# Power_Buggy_EFI_V3_1.net
KiCad netlist of a schematic drawn in EAGLE
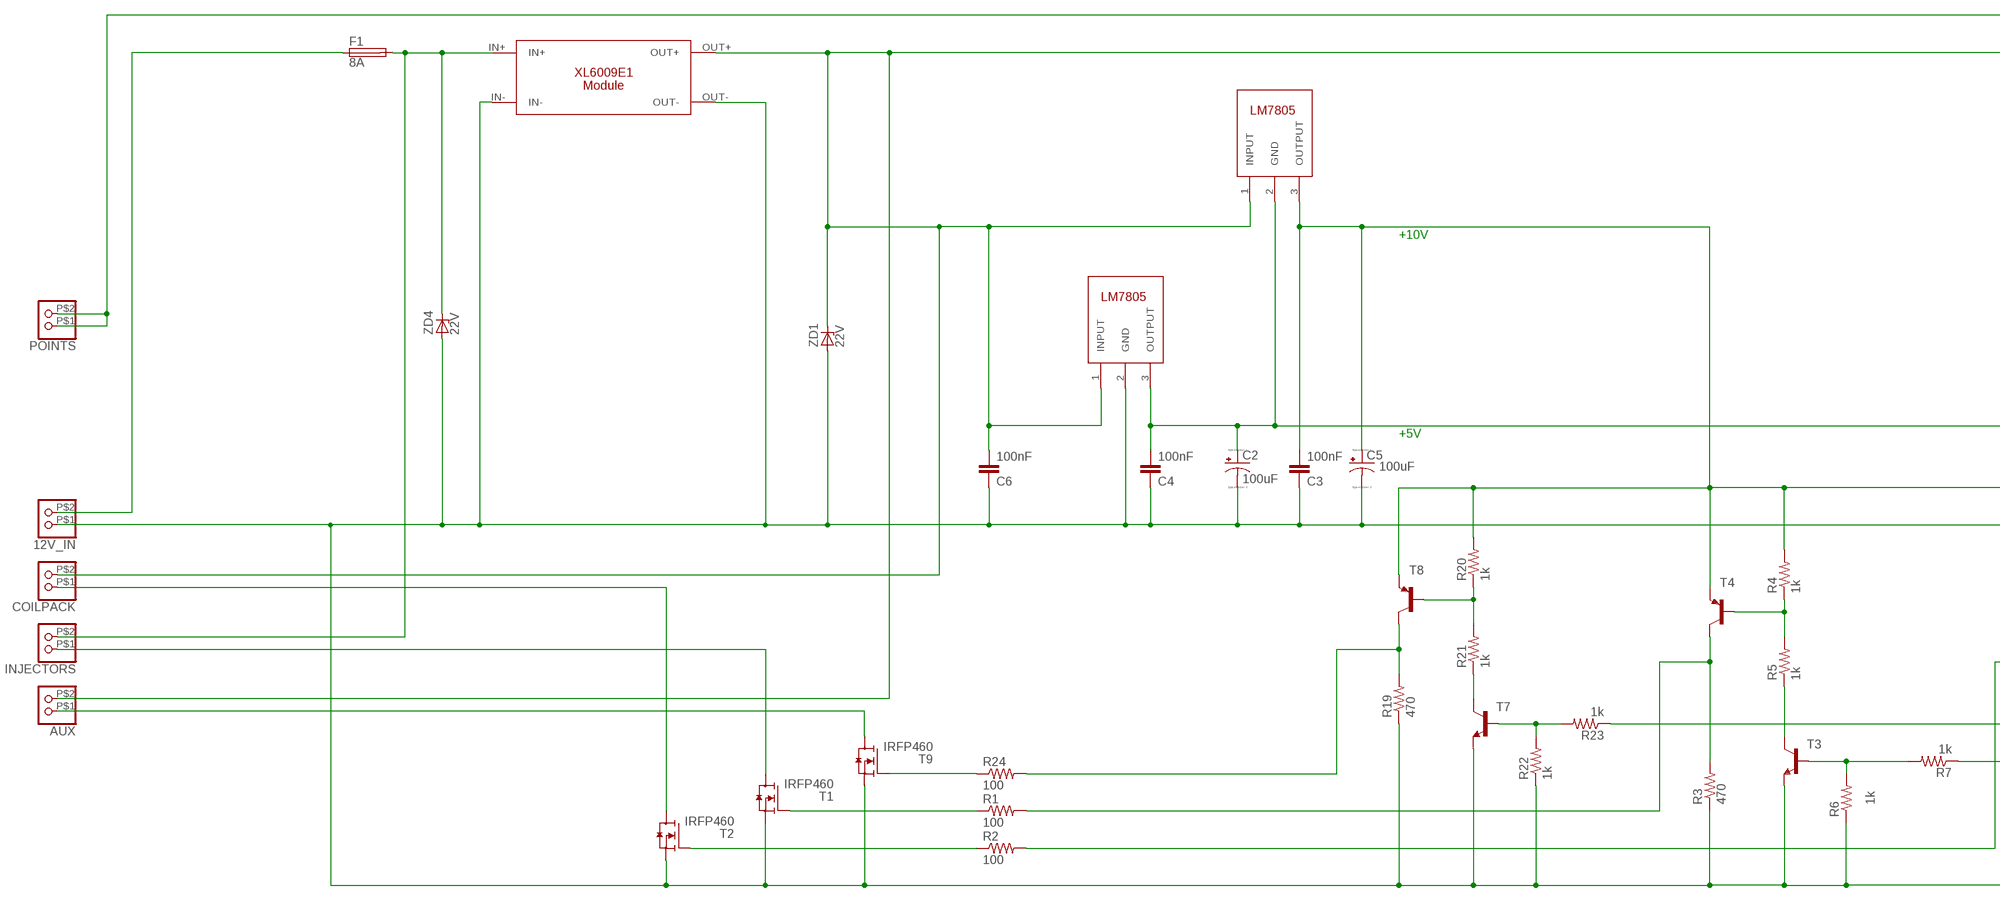
[diagram p0: schematic, sheet 1, part 1 of 2]
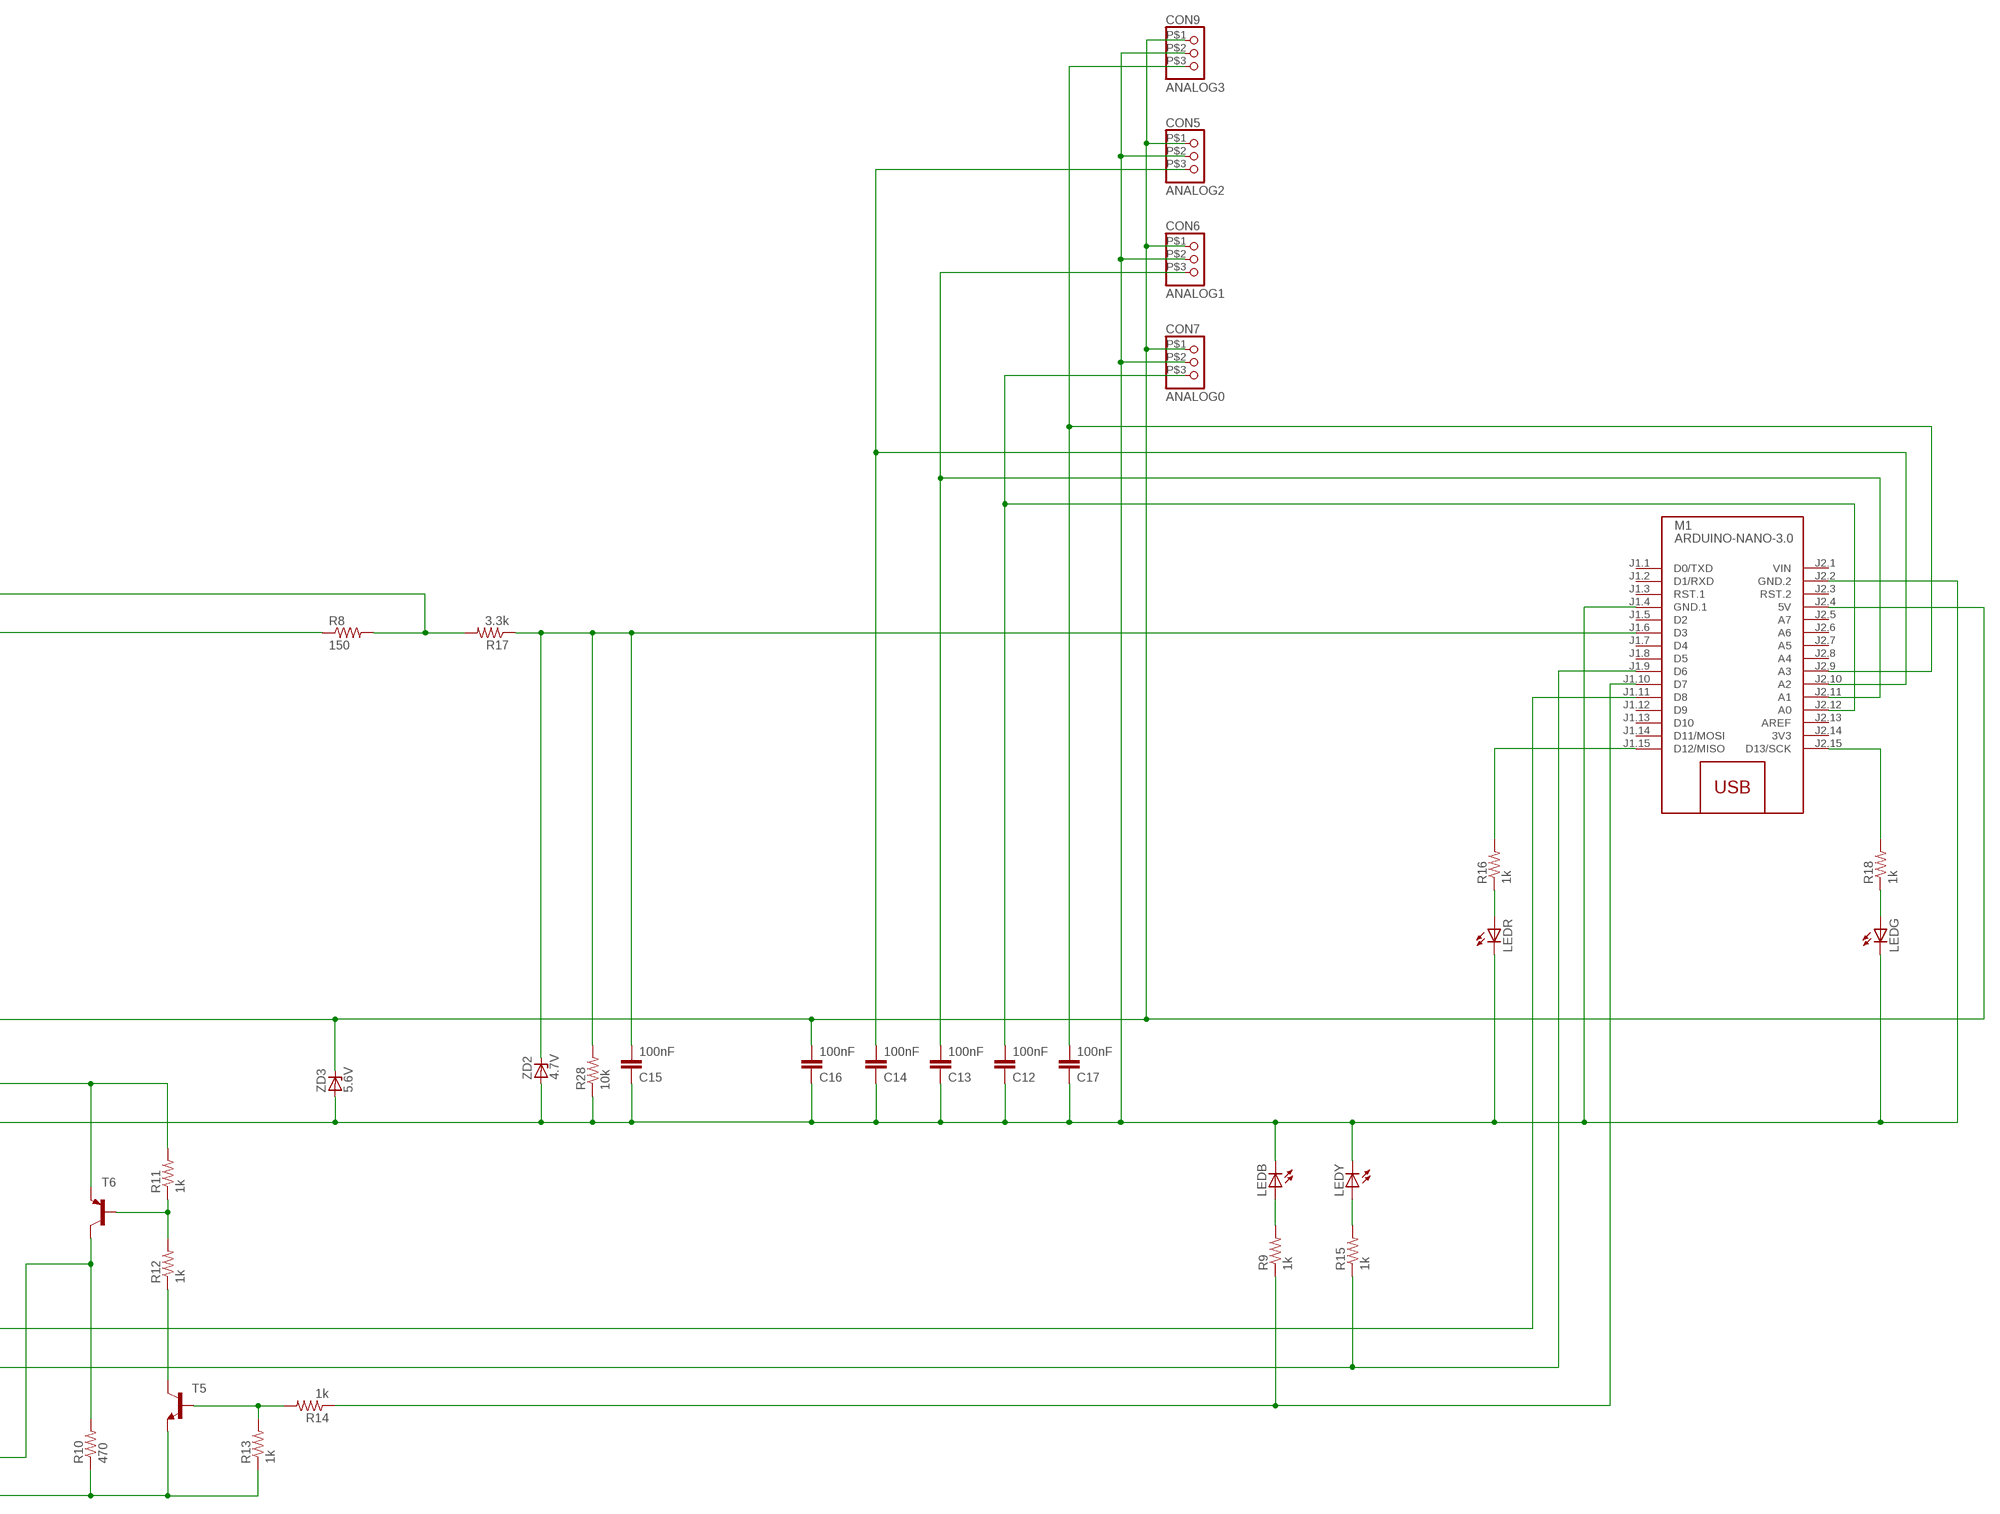
[diagram p1: schematic, sheet 1, part 2 of 2]

(export (version "E")
  (design (tool "Eeschema 10.0.6"))
  (components
    (comp (ref "12V_IN")
      (value "EBBA-02-C-SS-BU")
      (footprint "eagle-import:EBBA-02-C-SS-BU")
      (libsource (lib "eagle-import") (part "EBBA-02-C-SS-BU"))
    )
    (comp (ref "AUX")
      (value "EBBA-02-C-SS-BU")
      (footprint "eagle-import:EBBA-02-C-SS-BU")
      (libsource (lib "eagle-import") (part "EBBA-02-C-SS-BU"))
    )
    (comp (ref "C2")
      (value "100uF")
      (footprint "eagle-import:E2-5")
      (libsource (lib "eagle-import") (part "CPOL-USE2-5"))
    )
    (comp (ref "C3")
      (value "100nF")
      (footprint "eagle-import:C050-025X075")
      (libsource (lib "eagle-import") (part "C-EU050-025X075"))
    )
    (comp (ref "C4")
      (value "100nF")
      (footprint "eagle-import:C050-025X075")
      (libsource (lib "eagle-import") (part "C-EU050-025X075"))
    )
    (comp (ref "C5")
      (value "100uF")
      (footprint "eagle-import:E2-5")
      (libsource (lib "eagle-import") (part "CPOL-USE2-5"))
    )
    (comp (ref "C6")
      (value "100nF")
      (footprint "eagle-import:C050-025X075")
      (libsource (lib "eagle-import") (part "C-EU050-025X075"))
    )
    (comp (ref "C12")
      (value "100nF")
      (footprint "eagle-import:C050-025X075")
      (libsource (lib "eagle-import") (part "C-EU050-025X075"))
    )
    (comp (ref "C13")
      (value "100nF")
      (footprint "eagle-import:C050-025X075")
      (libsource (lib "eagle-import") (part "C-EU050-025X075"))
    )
    (comp (ref "C14")
      (value "100nF")
      (footprint "eagle-import:C050-025X075")
      (libsource (lib "eagle-import") (part "C-EU050-025X075"))
    )
    (comp (ref "C15")
      (value "100nF")
      (footprint "eagle-import:C050-025X075")
      (libsource (lib "eagle-import") (part "C-EU050-025X075"))
    )
    (comp (ref "C16")
      (value "100nF")
      (footprint "eagle-import:C050-025X075")
      (libsource (lib "eagle-import") (part "C-EU050-025X075"))
    )
    (comp (ref "C17")
      (value "100nF")
      (footprint "eagle-import:C050-025X075")
      (libsource (lib "eagle-import") (part "C-EU050-025X075"))
    )
    (comp (ref "COILPACK")
      (value "EBBA-02-C-SS-BU")
      (footprint "eagle-import:EBBA-02-C-SS-BU")
      (libsource (lib "eagle-import") (part "EBBA-02-C-SS-BU"))
    )
    (comp (ref "CON5")
      (value "ANALOG2")
      (footprint "eagle-import:2.0MM_X3")
      (libsource (lib "eagle-import") (part "2.0MM_X3"))
    )
    (comp (ref "CON6")
      (value "ANALOG1")
      (footprint "eagle-import:2.0MM_X3")
      (libsource (lib "eagle-import") (part "2.0MM_X3"))
    )
    (comp (ref "CON7")
      (value "ANALOG0")
      (footprint "eagle-import:2.0MM_X3")
      (libsource (lib "eagle-import") (part "2.0MM_X3"))
    )
    (comp (ref "CON9")
      (value "ANALOG3")
      (footprint "eagle-import:2.0MM_X3")
      (libsource (lib "eagle-import") (part "2.0MM_X3"))
    )
    (comp (ref "F1")
      (value "8A")
      (footprint "eagle-import:GSH15")
      (fields (field (name "MPN") "64900001039"))
      (libsource (lib "eagle-import") (part "GSH15"))
    )
    (comp (ref "INJECTORS")
      (value "EBBA-02-C-SS-BU")
      (footprint "eagle-import:EBBA-02-C-SS-BU")
      (libsource (lib "eagle-import") (part "EBBA-02-C-SS-BU"))
    )
    (comp (ref "LEDB")
      (value "LED3MM")
      (footprint "eagle-import:LED3MM")
      (libsource (lib "eagle-import") (part "LED3MM"))
    )
    (comp (ref "LEDG")
      (value "LED3MM")
      (footprint "eagle-import:LED3MM")
      (libsource (lib "eagle-import") (part "LED3MM"))
    )
    (comp (ref "LEDR")
      (value "LED3MM")
      (footprint "eagle-import:LED3MM")
      (libsource (lib "eagle-import") (part "LED3MM"))
    )
    (comp (ref "LEDY")
      (value "LED3MM")
      (footprint "eagle-import:LED3MM")
      (libsource (lib "eagle-import") (part "LED3MM"))
    )
    (comp (ref "M1")
      (value "ARDUINO-NANO-3.0")
      (footprint "eagle-import:ARDUINO-NANO-3.0")
      (libsource (lib "eagle-import") (part "ARDUINO-NANO-3.0"))
    )
    (comp (ref "POINTS")
      (value "EBBA-02-C-SS-BU")
      (footprint "eagle-import:EBBA-02-C-SS-BU")
      (libsource (lib "eagle-import") (part "EBBA-02-C-SS-BU"))
    )
    (comp (ref "R1")
      (value "100")
      (footprint "eagle-import:0207_10")
      (libsource (lib "eagle-import") (part "R-US_0207/10"))
    )
    (comp (ref "R2")
      (value "100")
      (footprint "eagle-import:0207_10")
      (libsource (lib "eagle-import") (part "R-US_0207/10"))
    )
    (comp (ref "R3")
      (value "470")
      (footprint "eagle-import:0207_10")
      (libsource (lib "eagle-import") (part "R-US_0207/10"))
    )
    (comp (ref "R4")
      (value "1k")
      (footprint "eagle-import:0207_10")
      (libsource (lib "eagle-import") (part "R-US_0207/10"))
    )
    (comp (ref "R5")
      (value "1k")
      (footprint "eagle-import:0207_10")
      (libsource (lib "eagle-import") (part "R-US_0207/10"))
    )
    (comp (ref "R6")
      (value "1k")
      (footprint "eagle-import:0207_10")
      (libsource (lib "eagle-import") (part "R-US_0207/10"))
    )
    (comp (ref "R7")
      (value "1k")
      (footprint "eagle-import:0207_10")
      (libsource (lib "eagle-import") (part "R-US_0207/10"))
    )
    (comp (ref "R8")
      (value "150")
      (footprint "eagle-import:0617_22")
      (libsource (lib "eagle-import") (part "R-US_0617/22"))
    )
    (comp (ref "R9")
      (value "1k")
      (footprint "eagle-import:0207_10")
      (libsource (lib "eagle-import") (part "R-US_0207/10"))
    )
    (comp (ref "R10")
      (value "470")
      (footprint "eagle-import:0207_10")
      (libsource (lib "eagle-import") (part "R-US_0207/10"))
    )
    (comp (ref "R11")
      (value "1k")
      (footprint "eagle-import:0207_10")
      (libsource (lib "eagle-import") (part "R-US_0207/10"))
    )
    (comp (ref "R12")
      (value "1k")
      (footprint "eagle-import:0207_10")
      (libsource (lib "eagle-import") (part "R-US_0207/10"))
    )
    (comp (ref "R13")
      (value "1k")
      (footprint "eagle-import:0207_10")
      (libsource (lib "eagle-import") (part "R-US_0207/10"))
    )
    (comp (ref "R14")
      (value "1k")
      (footprint "eagle-import:0207_10")
      (libsource (lib "eagle-import") (part "R-US_0207/10"))
    )
    (comp (ref "R15")
      (value "1k")
      (footprint "eagle-import:0207_10")
      (libsource (lib "eagle-import") (part "R-US_0207/10"))
    )
    (comp (ref "R16")
      (value "1k")
      (footprint "eagle-import:0207_10")
      (libsource (lib "eagle-import") (part "R-US_0207/10"))
    )
    (comp (ref "R17")
      (value "3.3k")
      (footprint "eagle-import:0207_10")
      (libsource (lib "eagle-import") (part "R-US_0207/10"))
    )
    (comp (ref "R18")
      (value "1k")
      (footprint "eagle-import:0207_10")
      (libsource (lib "eagle-import") (part "R-US_0207/10"))
    )
    (comp (ref "R19")
      (value "470")
      (footprint "eagle-import:0207_10")
      (libsource (lib "eagle-import") (part "R-US_0207/10"))
    )
    (comp (ref "R20")
      (value "1k")
      (footprint "eagle-import:0207_10")
      (libsource (lib "eagle-import") (part "R-US_0207/10"))
    )
    (comp (ref "R21")
      (value "1k")
      (footprint "eagle-import:0207_10")
      (libsource (lib "eagle-import") (part "R-US_0207/10"))
    )
    (comp (ref "R22")
      (value "1k")
      (footprint "eagle-import:0207_10")
      (libsource (lib "eagle-import") (part "R-US_0207/10"))
    )
    (comp (ref "R23")
      (value "1k")
      (footprint "eagle-import:0207_10")
      (libsource (lib "eagle-import") (part "R-US_0207/10"))
    )
    (comp (ref "R24")
      (value "100")
      (footprint "eagle-import:0207_10")
      (libsource (lib "eagle-import") (part "R-US_0207/10"))
    )
    (comp (ref "R28")
      (value "10k")
      (footprint "eagle-import:0207_10")
      (libsource (lib "eagle-import") (part "R-US_0207/10"))
    )
    (comp (ref "REG1")
      (value "LM7805_VERT")
      (footprint "eagle-import:TO220_VERT")
      (libsource (lib "eagle-import") (part "LM7805_VERT"))
    )
    (comp (ref "REG2")
      (value "LM7805_VERT")
      (footprint "eagle-import:TO220_VERT")
      (libsource (lib "eagle-import") (part "LM7805_VERT"))
    )
    (comp (ref "T1")
      (value "IRFP460")
      (footprint "eagle-import:TO-247_HORIZONTAL")
      (libsource (lib "eagle-import") (part "MOSFET_VERT"))
    )
    (comp (ref "T2")
      (value "IRFP460")
      (footprint "eagle-import:TO-247_HORIZONTAL")
      (libsource (lib "eagle-import") (part "MOSFET_VERT"))
    )
    (comp (ref "T3")
      (value "-NPN-TO92-EBC")
      (footprint "eagle-import:TO92-EBC")
      (libsource (lib "eagle-import") (part "-NPN-TO92-EBC"))
    )
    (comp (ref "T4")
      (value "BCX58-PNP-TO92-EBC")
      (footprint "eagle-import:TO92-EBC")
      (libsource (lib "eagle-import") (part "-PNP-TO92-EBCBCX58"))
    )
    (comp (ref "T5")
      (value "-NPN-TO92-EBC")
      (footprint "eagle-import:TO92-EBC")
      (libsource (lib "eagle-import") (part "-NPN-TO92-EBC"))
    )
    (comp (ref "T6")
      (value "BCX58-PNP-TO92-EBC")
      (footprint "eagle-import:TO92-EBC")
      (libsource (lib "eagle-import") (part "-PNP-TO92-EBCBCX58"))
    )
    (comp (ref "T7")
      (value "-NPN-TO92-EBC")
      (footprint "eagle-import:TO92-EBC")
      (libsource (lib "eagle-import") (part "-NPN-TO92-EBC"))
    )
    (comp (ref "T8")
      (value "BCX58-PNP-TO92-EBC")
      (footprint "eagle-import:TO92-EBC")
      (libsource (lib "eagle-import") (part "-PNP-TO92-EBCBCX58"))
    )
    (comp (ref "T9")
      (value "IRFP460")
      (footprint "eagle-import:TO-247_HORIZONTAL")
      (libsource (lib "eagle-import") (part "MOSFET_VERT"))
    )
    (comp (ref "U$2")
      (value "XL6009E1_MOD")
      (footprint "eagle-import:XL6009E1_MOD")
      (libsource (lib "eagle-import") (part "XL6009E1_MOD"))
    )
    (comp (ref "ZD1")
      (value "22V")
      (footprint "eagle-import:C1702-15")
      (libsource (lib "eagle-import") (part "1N5333"))
    )
    (comp (ref "ZD2")
      (value "4.7V")
      (footprint "eagle-import:DO41Z10")
      (libsource (lib "eagle-import") (part "1N4728"))
    )
    (comp (ref "ZD3")
      (value "5.6V")
      (footprint "eagle-import:C1702-15")
      (libsource (lib "eagle-import") (part "1N5333"))
    )
    (comp (ref "ZD4")
      (value "22V")
      (footprint "eagle-import:C1702-15")
      (libsource (lib "eagle-import") (part "1N5333"))
    )
  )
  (nets
    (net (code "1") (name "/3V3") (class "Default")
      (node (ref "M1") (pin "J2.14") (pinfunction "3V3_J2.14") (pintype "power_in"))
    )
    (net (code "2") (name "/VIN") (class "Default")
      (node (ref "M1") (pin "J2.1") (pinfunction "VIN_J2.1") (pintype "power_in"))
    )
    (net (code "3") (name "Net-(12V_IN-1)") (class "Default")
      (node (ref "12V_IN") (pin "P$1") (pinfunction "1_P$1") (pintype "passive"))
      (node (ref "C12") (pin "1") (pinfunction "1_1") (pintype "passive"))
      (node (ref "C13") (pin "1") (pinfunction "1_1") (pintype "passive"))
      (node (ref "C14") (pin "1") (pinfunction "1_1") (pintype "passive"))
      (node (ref "C15") (pin "1") (pinfunction "1_1") (pintype "passive"))
      (node (ref "C16") (pin "1") (pinfunction "1_1") (pintype "passive"))
      (node (ref "C17") (pin "1") (pinfunction "1_1") (pintype "passive"))
      (node (ref "C2") (pin "-") (pinfunction "-_-") (pintype "passive"))
      (node (ref "C3") (pin "1") (pinfunction "1_1") (pintype "passive"))
      (node (ref "C4") (pin "1") (pinfunction "1_1") (pintype "passive"))
      (node (ref "C5") (pin "-") (pinfunction "-_-") (pintype "passive"))
      (node (ref "C6") (pin "1") (pinfunction "1_1") (pintype "passive"))
      (node (ref "CON5") (pin "P$2") (pinfunction "2_P$2") (pintype "passive"))
      (node (ref "CON6") (pin "P$2") (pinfunction "2_P$2") (pintype "passive"))
      (node (ref "CON7") (pin "P$2") (pinfunction "2_P$2") (pintype "passive"))
      (node (ref "CON9") (pin "P$2") (pinfunction "2_P$2") (pintype "passive"))
      (node (ref "LEDB") (pin "K") (pinfunction "C_K") (pintype "passive"))
      (node (ref "LEDG") (pin "K") (pinfunction "C_K") (pintype "passive"))
      (node (ref "LEDR") (pin "K") (pinfunction "C_K") (pintype "passive"))
      (node (ref "LEDY") (pin "K") (pinfunction "C_K") (pintype "passive"))
      (node (ref "M1") (pin "J1.4") (pinfunction "GND.1_J1.4") (pintype "power_in"))
      (node (ref "M1") (pin "J2.2") (pinfunction "GND.2_J2.2") (pintype "power_in"))
      (node (ref "R10") (pin "1") (pinfunction "1_1") (pintype "passive"))
      (node (ref "R13") (pin "1") (pinfunction "1_1") (pintype "passive"))
      (node (ref "R19") (pin "1") (pinfunction "1_1") (pintype "passive"))
      (node (ref "R22") (pin "1") (pinfunction "1_1") (pintype "passive"))
      (node (ref "R28") (pin "1") (pinfunction "1_1") (pintype "passive"))
      (node (ref "R3") (pin "1") (pinfunction "1_1") (pintype "passive"))
      (node (ref "R6") (pin "1") (pinfunction "1_1") (pintype "passive"))
      (node (ref "REG1") (pin "2") (pinfunction "GND_2") (pintype "bidirectional"))
      (node (ref "T1") (pin "S") (pinfunction "S_S") (pintype "passive"))
      (node (ref "T2") (pin "S") (pinfunction "S_S") (pintype "passive"))
      (node (ref "T3") (pin "E") (pinfunction "E_E") (pintype "passive"))
      (node (ref "T5") (pin "E") (pinfunction "E_E") (pintype "passive"))
      (node (ref "T7") (pin "E") (pinfunction "E_E") (pintype "passive"))
      (node (ref "T9") (pin "S") (pinfunction "S_S") (pintype "passive"))
      (node (ref "U$2") (pin "IN-") (pinfunction "IN-_IN-") (pintype "bidirectional"))
      (node (ref "U$2") (pin "OUT-") (pinfunction "OUT-_OUT-") (pintype "bidirectional"))
      (node (ref "ZD1") (pin "A") (pinfunction "A_A") (pintype "passive"))
      (node (ref "ZD2") (pin "A") (pinfunction "A_A") (pintype "passive"))
      (node (ref "ZD3") (pin "A") (pinfunction "A_A") (pintype "passive"))
      (node (ref "ZD4") (pin "A") (pinfunction "A_A") (pintype "passive"))
    )
    (net (code "4") (name "Net-(12V_IN-2)") (class "Default")
      (node (ref "12V_IN") (pin "P$2") (pinfunction "2_P$2") (pintype "passive"))
      (node (ref "F1") (pin "1") (pinfunction "1_1") (pintype "passive"))
    )
    (net (code "5") (name "Net-(AUX-1)") (class "Default")
      (node (ref "AUX") (pin "P$1") (pinfunction "1_P$1") (pintype "passive"))
      (node (ref "T9") (pin "D") (pinfunction "D_D") (pintype "passive"))
    )
    (net (code "6") (name "Net-(AUX-2)") (class "Default")
      (node (ref "AUX") (pin "P$2") (pinfunction "2_P$2") (pintype "passive"))
      (node (ref "C6") (pin "2") (pinfunction "2_2") (pintype "passive"))
      (node (ref "COILPACK") (pin "P$2") (pinfunction "2_P$2") (pintype "passive"))
      (node (ref "R8") (pin "1") (pinfunction "1_1") (pintype "passive"))
      (node (ref "REG1") (pin "1") (pinfunction "INPUT_1") (pintype "bidirectional"))
      (node (ref "REG2") (pin "1") (pinfunction "INPUT_1") (pintype "bidirectional"))
      (node (ref "U$2") (pin "OUT+") (pinfunction "OUT+_OUT+") (pintype "bidirectional"))
      (node (ref "ZD1") (pin "C") (pinfunction "C_C") (pintype "passive"))
    )
    (net (code "7") (name "Net-(COILPACK-1)") (class "Default")
      (node (ref "COILPACK") (pin "P$1") (pinfunction "1_P$1") (pintype "passive"))
      (node (ref "T2") (pin "D") (pinfunction "D_D") (pintype "passive"))
    )
    (net (code "8") (name "Net-(CON5-1)") (class "Default")
      (node (ref "C16") (pin "2") (pinfunction "2_2") (pintype "passive"))
      (node (ref "C2") (pin "+") (pinfunction "+_+") (pintype "passive"))
      (node (ref "C4") (pin "2") (pinfunction "2_2") (pintype "passive"))
      (node (ref "CON5") (pin "P$1") (pinfunction "1_P$1") (pintype "passive"))
      (node (ref "CON6") (pin "P$1") (pinfunction "1_P$1") (pintype "passive"))
      (node (ref "CON7") (pin "P$1") (pinfunction "1_P$1") (pintype "passive"))
      (node (ref "CON9") (pin "P$1") (pinfunction "1_P$1") (pintype "passive"))
      (node (ref "M1") (pin "J2.4") (pinfunction "5V_J2.4") (pintype "power_in"))
      (node (ref "REG1") (pin "3") (pinfunction "OUTPUT_3") (pintype "bidirectional"))
      (node (ref "REG2") (pin "2") (pinfunction "GND_2") (pintype "bidirectional"))
      (node (ref "ZD3") (pin "C") (pinfunction "C_C") (pintype "passive"))
    )
    (net (code "9") (name "Net-(CON5-3)") (class "Default")
      (node (ref "C14") (pin "2") (pinfunction "2_2") (pintype "passive"))
      (node (ref "CON5") (pin "P$3") (pinfunction "3_P$3") (pintype "passive"))
      (node (ref "M1") (pin "J2.10") (pinfunction "A2_J2.10") (pintype "bidirectional"))
    )
    (net (code "10") (name "Net-(CON6-3)") (class "Default")
      (node (ref "C13") (pin "2") (pinfunction "2_2") (pintype "passive"))
      (node (ref "CON6") (pin "P$3") (pinfunction "3_P$3") (pintype "passive"))
      (node (ref "M1") (pin "J2.11") (pinfunction "A1_J2.11") (pintype "bidirectional"))
    )
    (net (code "11") (name "Net-(CON7-3)") (class "Default")
      (node (ref "C12") (pin "2") (pinfunction "2_2") (pintype "passive"))
      (node (ref "CON7") (pin "P$3") (pinfunction "3_P$3") (pintype "passive"))
      (node (ref "M1") (pin "J2.12") (pinfunction "A0_J2.12") (pintype "bidirectional"))
    )
    (net (code "12") (name "Net-(CON9-3)") (class "Default")
      (node (ref "C17") (pin "2") (pinfunction "2_2") (pintype "passive"))
      (node (ref "CON9") (pin "P$3") (pinfunction "3_P$3") (pintype "passive"))
      (node (ref "M1") (pin "J2.9") (pinfunction "A3_J2.9") (pintype "bidirectional"))
    )
    (net (code "13") (name "Net-(INJECTORS-1)") (class "Default")
      (node (ref "INJECTORS") (pin "P$1") (pinfunction "1_P$1") (pintype "passive"))
      (node (ref "T1") (pin "D") (pinfunction "D_D") (pintype "passive"))
    )
    (net (code "14") (name "Net-(INJECTORS-2)") (class "Default")
      (node (ref "F1") (pin "2") (pinfunction "2_2") (pintype "passive"))
      (node (ref "INJECTORS") (pin "P$2") (pinfunction "2_P$2") (pintype "passive"))
      (node (ref "U$2") (pin "IN+") (pinfunction "IN+_IN+") (pintype "bidirectional"))
      (node (ref "ZD4") (pin "C") (pinfunction "C_C") (pintype "passive"))
    )
    (net (code "15") (name "Net-(LEDB-PadA)") (class "Default")
      (node (ref "LEDB") (pin "A") (pinfunction "A_A") (pintype "passive"))
      (node (ref "R9") (pin "2") (pinfunction "2_2") (pintype "passive"))
    )
    (net (code "16") (name "Net-(LEDG-PadA)") (class "Default")
      (node (ref "LEDG") (pin "A") (pinfunction "A_A") (pintype "passive"))
      (node (ref "R18") (pin "1") (pinfunction "1_1") (pintype "passive"))
    )
    (net (code "17") (name "Net-(LEDR-PadA)") (class "Default")
      (node (ref "LEDR") (pin "A") (pinfunction "A_A") (pintype "passive"))
      (node (ref "R16") (pin "1") (pinfunction "1_1") (pintype "passive"))
    )
    (net (code "18") (name "Net-(LEDY-PadA)") (class "Default")
      (node (ref "LEDY") (pin "A") (pinfunction "A_A") (pintype "passive"))
      (node (ref "R15") (pin "2") (pinfunction "2_2") (pintype "passive"))
    )
    (net (code "19") (name "Net-(M1-D3)") (class "Default")
      (node (ref "C15") (pin "2") (pinfunction "2_2") (pintype "passive"))
      (node (ref "M1") (pin "J1.6") (pinfunction "D3_J1.6") (pintype "bidirectional"))
      (node (ref "R17") (pin "1") (pinfunction "1_1") (pintype "passive"))
      (node (ref "R28") (pin "2") (pinfunction "2_2") (pintype "passive"))
      (node (ref "ZD2") (pin "C") (pinfunction "C_C") (pintype "passive"))
    )
    (net (code "20") (name "Net-(M1-D6)") (class "Default")
      (node (ref "M1") (pin "J1.9") (pinfunction "D6_J1.9") (pintype "bidirectional"))
      (node (ref "R15") (pin "1") (pinfunction "1_1") (pintype "passive"))
      (node (ref "R7") (pin "1") (pinfunction "1_1") (pintype "passive"))
    )
    (net (code "21") (name "Net-(M1-D7)") (class "Default")
      (node (ref "M1") (pin "J1.10") (pinfunction "D7_J1.10") (pintype "bidirectional"))
      (node (ref "R14") (pin "1") (pinfunction "1_1") (pintype "passive"))
      (node (ref "R9") (pin "1") (pinfunction "1_1") (pintype "passive"))
    )
    (net (code "22") (name "Net-(M1-D8)") (class "Default")
      (node (ref "M1") (pin "J1.11") (pinfunction "D8_J1.11") (pintype "bidirectional"))
      (node (ref "R23") (pin "1") (pinfunction "1_1") (pintype "passive"))
    )
    (net (code "23") (name "Net-(M1-D12{slash}MISO)") (class "Default")
      (node (ref "M1") (pin "J1.15") (pinfunction "D12/MISO_J1.15") (pintype "bidirectional"))
      (node (ref "R16") (pin "2") (pinfunction "2_2") (pintype "passive"))
    )
    (net (code "24") (name "Net-(M1-D13{slash}SCK)") (class "Default")
      (node (ref "M1") (pin "J2.15") (pinfunction "D13/SCK_J2.15") (pintype "bidirectional"))
      (node (ref "R18") (pin "2") (pinfunction "2_2") (pintype "passive"))
    )
    (net (code "25") (name "Net-(POINTS-1)") (class "Default")
      (node (ref "POINTS") (pin "P$1") (pinfunction "1_P$1") (pintype "passive"))
      (node (ref "POINTS") (pin "P$2") (pinfunction "2_P$2") (pintype "passive"))
      (node (ref "R17") (pin "2") (pinfunction "2_2") (pintype "passive"))
      (node (ref "R8") (pin "2") (pinfunction "2_2") (pintype "passive"))
    )
    (net (code "26") (name "Net-(R1-Pad1)") (class "Default")
      (node (ref "R1") (pin "1") (pinfunction "1_1") (pintype "passive"))
      (node (ref "T1") (pin "G") (pinfunction "G_G") (pintype "passive"))
    )
    (net (code "27") (name "Net-(R1-Pad2)") (class "Default")
      (node (ref "R1") (pin "2") (pinfunction "2_2") (pintype "passive"))
      (node (ref "R3") (pin "2") (pinfunction "2_2") (pintype "passive"))
      (node (ref "T4") (pin "C") (pinfunction "C_C") (pintype "passive"))
    )
    (net (code "28") (name "Net-(R2-Pad1)") (class "Default")
      (node (ref "R2") (pin "1") (pinfunction "1_1") (pintype "passive"))
      (node (ref "T2") (pin "G") (pinfunction "G_G") (pintype "passive"))
    )
    (net (code "29") (name "Net-(R4-Pad1)") (class "Default")
      (node (ref "R4") (pin "1") (pinfunction "1_1") (pintype "passive"))
      (node (ref "R5") (pin "2") (pinfunction "2_2") (pintype "passive"))
      (node (ref "T4") (pin "B") (pinfunction "B_B") (pintype "passive"))
    )
    (net (code "30") (name "Net-(R5-Pad1)") (class "Default")
      (node (ref "R5") (pin "1") (pinfunction "1_1") (pintype "passive"))
      (node (ref "T3") (pin "C") (pinfunction "C_C") (pintype "passive"))
    )
    (net (code "31") (name "Net-(R6-Pad2)") (class "Default")
      (node (ref "R6") (pin "2") (pinfunction "2_2") (pintype "passive"))
      (node (ref "R7") (pin "2") (pinfunction "2_2") (pintype "passive"))
      (node (ref "T3") (pin "B") (pinfunction "B_B") (pintype "passive"))
    )
    (net (code "32") (name "Net-(R10-Pad2)") (class "Default")
      (node (ref "R10") (pin "2") (pinfunction "2_2") (pintype "passive"))
      (node (ref "R2") (pin "2") (pinfunction "2_2") (pintype "passive"))
      (node (ref "T6") (pin "C") (pinfunction "C_C") (pintype "passive"))
    )
    (net (code "33") (name "Net-(R11-Pad1)") (class "Default")
      (node (ref "R11") (pin "1") (pinfunction "1_1") (pintype "passive"))
      (node (ref "R12") (pin "2") (pinfunction "2_2") (pintype "passive"))
      (node (ref "T6") (pin "B") (pinfunction "B_B") (pintype "passive"))
    )
    (net (code "34") (name "Net-(R12-Pad1)") (class "Default")
      (node (ref "R12") (pin "1") (pinfunction "1_1") (pintype "passive"))
      (node (ref "T5") (pin "C") (pinfunction "C_C") (pintype "passive"))
    )
    (net (code "35") (name "Net-(R13-Pad2)") (class "Default")
      (node (ref "R13") (pin "2") (pinfunction "2_2") (pintype "passive"))
      (node (ref "R14") (pin "2") (pinfunction "2_2") (pintype "passive"))
      (node (ref "T5") (pin "B") (pinfunction "B_B") (pintype "passive"))
    )
    (net (code "36") (name "Net-(R19-Pad2)") (class "Default")
      (node (ref "R19") (pin "2") (pinfunction "2_2") (pintype "passive"))
      (node (ref "R24") (pin "2") (pinfunction "2_2") (pintype "passive"))
      (node (ref "T8") (pin "C") (pinfunction "C_C") (pintype "passive"))
    )
    (net (code "37") (name "Net-(R20-Pad1)") (class "Default")
      (node (ref "R20") (pin "1") (pinfunction "1_1") (pintype "passive"))
      (node (ref "R21") (pin "2") (pinfunction "2_2") (pintype "passive"))
      (node (ref "T8") (pin "B") (pinfunction "B_B") (pintype "passive"))
    )
    (net (code "38") (name "Net-(R21-Pad1)") (class "Default")
      (node (ref "R21") (pin "1") (pinfunction "1_1") (pintype "passive"))
      (node (ref "T7") (pin "C") (pinfunction "C_C") (pintype "passive"))
    )
    (net (code "39") (name "Net-(R22-Pad2)") (class "Default")
      (node (ref "R22") (pin "2") (pinfunction "2_2") (pintype "passive"))
      (node (ref "R23") (pin "2") (pinfunction "2_2") (pintype "passive"))
      (node (ref "T7") (pin "B") (pinfunction "B_B") (pintype "passive"))
    )
    (net (code "40") (name "Net-(R24-Pad1)") (class "Default")
      (node (ref "R24") (pin "1") (pinfunction "1_1") (pintype "passive"))
      (node (ref "T9") (pin "G") (pinfunction "G_G") (pintype "passive"))
    )
    (net (code "41") (name "Net-(REG2-OUTPUT)") (class "Default")
      (node (ref "C3") (pin "2") (pinfunction "2_2") (pintype "passive"))
      (node (ref "C5") (pin "+") (pinfunction "+_+") (pintype "passive"))
      (node (ref "R11") (pin "2") (pinfunction "2_2") (pintype "passive"))
      (node (ref "R20") (pin "2") (pinfunction "2_2") (pintype "passive"))
      (node (ref "R4") (pin "2") (pinfunction "2_2") (pintype "passive"))
      (node (ref "REG2") (pin "3") (pinfunction "OUTPUT_3") (pintype "bidirectional"))
      (node (ref "T4") (pin "E") (pinfunction "E_E") (pintype "passive"))
      (node (ref "T6") (pin "E") (pinfunction "E_E") (pintype "passive"))
      (node (ref "T8") (pin "E") (pinfunction "E_E") (pintype "passive"))
    )
    (net (code "42") (name "unconnected-(M1-A4-PadJ2.8)") (class "Default")
      (node (ref "M1") (pin "J2.8") (pinfunction "A4_J2.8") (pintype "bidirectional"))
    )
    (net (code "43") (name "unconnected-(M1-A5-PadJ2.7)") (class "Default")
      (node (ref "M1") (pin "J2.7") (pinfunction "A5_J2.7") (pintype "bidirectional"))
    )
    (net (code "44") (name "unconnected-(M1-A6-PadJ2.6)") (class "Default")
      (node (ref "M1") (pin "J2.6") (pinfunction "A6_J2.6") (pintype "bidirectional"))
    )
    (net (code "45") (name "unconnected-(M1-A7-PadJ2.5)") (class "Default")
      (node (ref "M1") (pin "J2.5") (pinfunction "A7_J2.5") (pintype "bidirectional"))
    )
    (net (code "46") (name "unconnected-(M1-AREF-PadJ2.13)") (class "Default")
      (node (ref "M1") (pin "J2.13") (pinfunction "AREF_J2.13") (pintype "bidirectional"))
    )
    (net (code "47") (name "unconnected-(M1-D0{slash}TXD-PadJ1.1)") (class "Default")
      (node (ref "M1") (pin "J1.1") (pinfunction "D0/TXD_J1.1") (pintype "bidirectional"))
    )
    (net (code "48") (name "unconnected-(M1-D1{slash}RXD-PadJ1.2)") (class "Default")
      (node (ref "M1") (pin "J1.2") (pinfunction "D1/RXD_J1.2") (pintype "bidirectional"))
    )
    (net (code "49") (name "unconnected-(M1-D2-PadJ1.5)") (class "Default")
      (node (ref "M1") (pin "J1.5") (pinfunction "D2_J1.5") (pintype "bidirectional"))
    )
    (net (code "50") (name "unconnected-(M1-D4-PadJ1.7)") (class "Default")
      (node (ref "M1") (pin "J1.7") (pinfunction "D4_J1.7") (pintype "bidirectional"))
    )
    (net (code "51") (name "unconnected-(M1-D5-PadJ1.8)") (class "Default")
      (node (ref "M1") (pin "J1.8") (pinfunction "D5_J1.8") (pintype "bidirectional"))
    )
    (net (code "52") (name "unconnected-(M1-D9-PadJ1.12)") (class "Default")
      (node (ref "M1") (pin "J1.12") (pinfunction "D9_J1.12") (pintype "bidirectional"))
    )
    (net (code "53") (name "unconnected-(M1-D10-PadJ1.13)") (class "Default")
      (node (ref "M1") (pin "J1.13") (pinfunction "D10_J1.13") (pintype "bidirectional"))
    )
    (net (code "54") (name "unconnected-(M1-D11{slash}MOSI-PadJ1.14)") (class "Default")
      (node (ref "M1") (pin "J1.14") (pinfunction "D11/MOSI_J1.14") (pintype "bidirectional"))
    )
    (net (code "55") (name "unconnected-(M1-RST.1-PadJ1.3)") (class "Default")
      (node (ref "M1") (pin "J1.3") (pinfunction "RST.1_J1.3") (pintype "bidirectional"))
    )
    (net (code "56") (name "unconnected-(M1-RST.2-PadJ2.3)") (class "Default")
      (node (ref "M1") (pin "J2.3") (pinfunction "RST.2_J2.3") (pintype "bidirectional"))
    )
  )
)
